# Power_Supply.net
KiCad netlist of a schematic drawn in Altium Designer
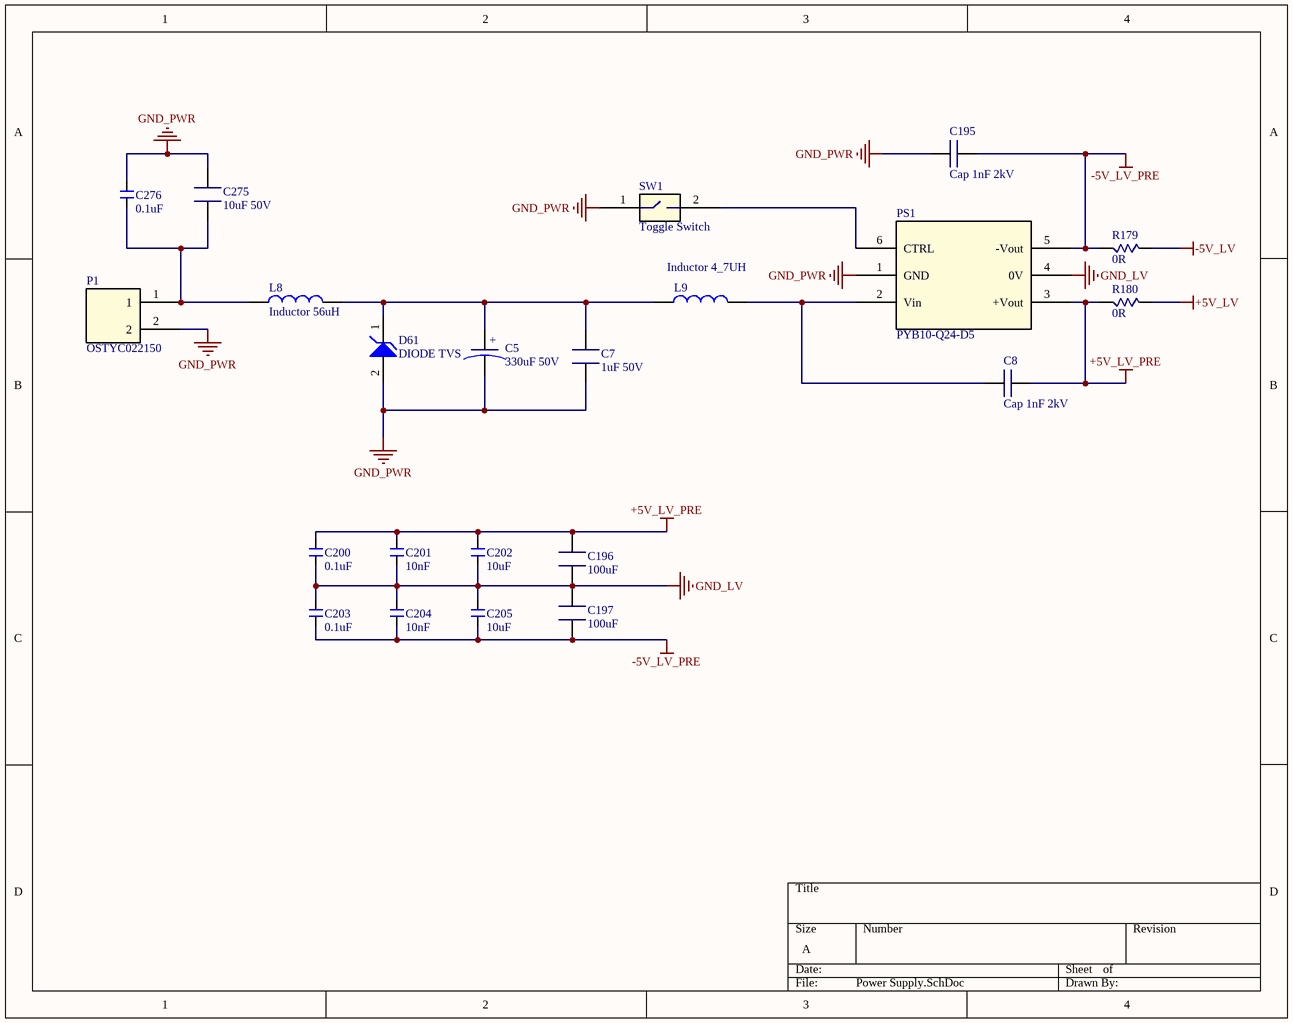
[diagram p0: Power Supply.SchDoc]

(export (version "E")
  (design (tool "Eeschema 10.0.6"))
  (components
    (comp (ref "C5")
      (value "330uF 50V")
      (footprint "Panasonic ECA-1HM331")
      (description "Capacitor Aluminum 330uF 50V")
      (fields (field (name "PART") "P5184-ND"))
      (libsource (lib "Library_Microgrid") (part "Cap Alum 330uF 50V"))
    )
    (comp (ref "C7")
      (value "1uF 50V")
      (footprint "1206")
      (description "CAP CER 1UF 50V X7R 1206")
      (fields (field (name "PART") "1276-1068-1-ND") (field (name "Comment") "Cap 1206"))
      (libsource (lib "Library_Microgrid") (part "Cap 1206"))
    )
    (comp (ref "C8")
      (value "Cap 1nF 2kV")
      (footprint "1812 (4532 Metric)")
      (description "CAP CER 1000PF 2KV X7R 1812")
      (fields (field (name "PART") "399-3447-1-ND"))
      (libsource (lib "Library_Microgrid") (part "Cap 3kV 220pF"))
    )
    (comp (ref "C195")
      (value "Cap 1nF 2kV")
      (footprint "1812 (4532 Metric)")
      (description "CAP CER 1000PF 2KV X7R 1812")
      (fields (field (name "PART") "399-3447-1-ND"))
      (libsource (lib "Library_Microgrid") (part "Cap 3kV 220pF"))
    )
    (comp (ref "C196")
      (value "100uF")
      (footprint "1206")
      (description "CAP CER 100UF 10V JB 1206")
      (fields (field (name "PART") "445-11682-1-ND") (field (name "Comment") "Cap 1206"))
      (libsource (lib "Library_Microgrid") (part "Cap 1206"))
    )
    (comp (ref "C197")
      (value "100uF")
      (footprint "1206")
      (description "CAP CER 100UF 10V JB 1206")
      (fields (field (name "PART") "445-11682-1-ND") (field (name "Comment") "Cap 1206"))
      (libsource (lib "Library_Microgrid") (part "Cap 1206"))
    )
    (comp (ref "C200")
      (value "0.1uF")
      (footprint "0603 (1608 Metric)")
      (description "CAP CER 0.1UF 50V Y5V 0603")
      (fields (field (name "PART") "311-1343-6-ND") (field (name "Comment") "Cap 0603_new"))
      (libsource (lib "Library_Microgrid") (part "Cap 0603_new"))
    )
    (comp (ref "C201")
      (value "10nF")
      (footprint "0603 (1608 Metric)")
      (description "CAP CER 0603 10NF 50V U2J 5%")
      (fields (field (name "PART") "399-13384-1-ND") (field (name "Comment") "Cap 0603_new"))
      (libsource (lib "Library_Microgrid") (part "Cap 0603_new"))
    )
    (comp (ref "C202")
      (value "10uF")
      (footprint "0603 (1608 Metric)")
      (description "CAP CER 10UF 35V X5R 0805")
      (fields (field (name "PART") "490-10515-1-ND") (field (name "Comment") "Cap 0603_new"))
      (libsource (lib "Library_Microgrid") (part "Cap 0603_new"))
    )
    (comp (ref "C203")
      (value "0.1uF")
      (footprint "0603 (1608 Metric)")
      (description "CAP CER 0.1UF 50V Y5V 0603")
      (fields (field (name "PART") "311-1343-6-ND") (field (name "Comment") "Cap 0603_new"))
      (libsource (lib "Library_Microgrid") (part "Cap 0603_new"))
    )
    (comp (ref "C204")
      (value "10nF")
      (footprint "0603 (1608 Metric)")
      (description "CAP CER 0603 10NF 50V U2J 5%")
      (fields (field (name "PART") "399-13384-1-ND") (field (name "Comment") "Cap 0603_new"))
      (libsource (lib "Library_Microgrid") (part "Cap 0603_new"))
    )
    (comp (ref "C205")
      (value "10uF")
      (footprint "0603 (1608 Metric)")
      (description "CAP CER 10UF 35V X5R 0805")
      (fields (field (name "PART") "490-10515-1-ND") (field (name "Comment") "Cap 0603_new"))
      (libsource (lib "Library_Microgrid") (part "Cap 0603_new"))
    )
    (comp (ref "C275")
      (value "10uF 50V")
      (footprint "1206")
      (description "CAP CER 10UF 50V X5R 1206")
      (fields (field (name "PART") "587-3248-1-ND") (field (name "Comment") "Cap 1206"))
      (libsource (lib "Library_Microgrid") (part "Cap 1206"))
    )
    (comp (ref "C276")
      (value "0.1uF")
      (footprint "0603 (1608 Metric)")
      (description "CAP CER 0.1UF 50V Y5V 0603")
      (fields (field (name "PART") "311-1343-6-ND") (field (name "Comment") "Cap 0603_new"))
      (libsource (lib "Library_Microgrid") (part "Cap 0603_new"))
    )
    (comp (ref "D61")
      (value "DIODE TVS")
      (footprint "SMCJ48A")
      (fields (field (name "PART") "495-2402-ND"))
      (libsource (lib "Library_Microgrid") (part "DIODE TVS"))
    )
    (comp (ref "L8")
      (value "Inductor 56uH")
      (footprint "Ind SM 56UH")
      (description "FIXED IND 56UH 700MA 481 MOHM")
      (fields (field (name "PART") "732-4102-1-ND"))
      (libsource (lib "Library_Microgrid") (part "Inductor 10uH"))
    )
    (comp (ref "L9")
      (value "Inductor 4_7UH")
      (footprint "Ind SM 4_7UH")
      (description "FIXED IND 4.7UH 1.2A 105 MOHM")
      (fields (field (name "PART") "732-1008-1-ND"))
      (libsource (lib "Library_Microgrid") (part "Inductor 10uH"))
    )
    (comp (ref "P1")
      (value "OSTYC022150")
      (footprint "2 pin Terminal")
      (description "2 pin Terminal")
      (fields (field (name "PART") "ED2902-ND"))
      (libsource (lib "Library_Microgrid") (part "2 pin Terminal"))
    )
    (comp (ref "PS1")
      (value "PYB10-Q24-D5")
      (footprint "6-DIP Module")
      (description "DC/DC CONVERTER +/-5V 10W")
      (fields (field (name "PART") "102-2849-ND"))
      (libsource (lib "Library_Microgrid") (part "PYB10-Q24-D5"))
    )
    (comp (ref "R179")
      (value "0R")
      (footprint "1206")
      (description "Resistor 1206")
      (libsource (lib "Library_Microgrid") (part "Resistor 1206"))
    )
    (comp (ref "R180")
      (value "0R")
      (footprint "1206")
      (description "Resistor 1206")
      (libsource (lib "Library_Microgrid") (part "Resistor 1206"))
    )
    (comp (ref "SW1")
      (value "Toggle Switch")
      (footprint "Toggle SW")
      (fields (field (name "PART") "360-3289-ND"))
      (libsource (lib "Library_Microgrid") (part "Toggle Switch"))
    )
  )
  (nets
    (net (code "1") (name "+5V_LV") (class "Default")
      (node (ref "R180") (pin "2") (pinfunction "A_2") (pintype "passive"))
    )
    (net (code "2") (name "+5V_LV_PRE") (class "Default")
      (node (ref "C196") (pin "2") (pinfunction "OUT_2") (pintype "passive"))
      (node (ref "C200") (pin "2") (pinfunction "OUT_2") (pintype "passive"))
      (node (ref "C201") (pin "2") (pinfunction "OUT_2") (pintype "passive"))
      (node (ref "C202") (pin "2") (pinfunction "OUT_2") (pintype "passive"))
      (node (ref "C8") (pin "2") (pinfunction "OUT_2") (pintype "passive"))
      (node (ref "PS1") (pin "3") (pinfunction "+Vout_3") (pintype "passive"))
      (node (ref "R180") (pin "1") (pinfunction "A_1") (pintype "passive"))
    )
    (net (code "3") (name "-5V_LV") (class "Default")
      (node (ref "R179") (pin "2") (pinfunction "A_2") (pintype "passive"))
    )
    (net (code "4") (name "-5V_LV_PRE") (class "Default")
      (node (ref "C195") (pin "2") (pinfunction "OUT_2") (pintype "passive"))
      (node (ref "C197") (pin "1") (pinfunction "OUT_1") (pintype "passive"))
      (node (ref "C203") (pin "1") (pinfunction "OUT_1") (pintype "passive"))
      (node (ref "C204") (pin "1") (pinfunction "OUT_1") (pintype "passive"))
      (node (ref "C205") (pin "1") (pinfunction "OUT_1") (pintype "passive"))
      (node (ref "PS1") (pin "5") (pinfunction "-Vout_5") (pintype "passive"))
      (node (ref "R179") (pin "1") (pinfunction "A_1") (pintype "passive"))
    )
    (net (code "5") (name "GND_LV") (class "Default")
      (node (ref "C196") (pin "1") (pinfunction "OUT_1") (pintype "passive"))
      (node (ref "C197") (pin "2") (pinfunction "OUT_2") (pintype "passive"))
      (node (ref "C200") (pin "1") (pinfunction "OUT_1") (pintype "passive"))
      (node (ref "C201") (pin "1") (pinfunction "OUT_1") (pintype "passive"))
      (node (ref "C202") (pin "1") (pinfunction "OUT_1") (pintype "passive"))
      (node (ref "C203") (pin "2") (pinfunction "OUT_2") (pintype "passive"))
      (node (ref "C204") (pin "2") (pinfunction "OUT_2") (pintype "passive"))
      (node (ref "C205") (pin "2") (pinfunction "OUT_2") (pintype "passive"))
      (node (ref "PS1") (pin "4") (pinfunction "0V_4") (pintype "passive"))
    )
    (net (code "6") (name "GND_PWR") (class "Default")
      (node (ref "C195") (pin "1") (pinfunction "OUT_1") (pintype "passive"))
      (node (ref "C275") (pin "2") (pinfunction "OUT_2") (pintype "passive"))
      (node (ref "C276") (pin "2") (pinfunction "OUT_2") (pintype "passive"))
      (node (ref "C5") (pin "2") (pinfunction "OUT_2") (pintype "passive"))
      (node (ref "C7") (pin "1") (pinfunction "OUT_1") (pintype "passive"))
      (node (ref "D61") (pin "2") (pinfunction "Anode_2") (pintype "passive"))
      (node (ref "P1") (pin "2") (pinfunction "2_2") (pintype "passive"))
      (node (ref "PS1") (pin "1") (pinfunction "GND_1") (pintype "passive"))
      (node (ref "SW1") (pin "1") (pinfunction "1_1") (pintype "passive"))
    )
    (net (code "7") (name "Net-(C5-OUT-Pad1)") (class "Default")
      (node (ref "C5") (pin "1") (pinfunction "OUT_1") (pintype "passive"))
      (node (ref "C7") (pin "2") (pinfunction "OUT_2") (pintype "passive"))
      (node (ref "D61") (pin "1") (pinfunction "Anode_1") (pintype "passive"))
      (node (ref "L8") (pin "2") (pinfunction "OUT_2") (pintype "passive"))
      (node (ref "L9") (pin "1") (pinfunction "OUT_1") (pintype "passive"))
    )
    (net (code "8") (name "Net-(C275-OUT-Pad1)") (class "Default")
      (node (ref "C275") (pin "1") (pinfunction "OUT_1") (pintype "passive"))
      (node (ref "C276") (pin "1") (pinfunction "OUT_1") (pintype "passive"))
      (node (ref "L8") (pin "1") (pinfunction "OUT_1") (pintype "passive"))
      (node (ref "P1") (pin "1") (pinfunction "1_1") (pintype "passive"))
    )
    (net (code "9") (name "Net-(PS1-CTRL)") (class "Default")
      (node (ref "PS1") (pin "6") (pinfunction "CTRL_6") (pintype "passive"))
      (node (ref "SW1") (pin "2") (pinfunction "2_2") (pintype "passive"))
    )
    (net (code "10") (name "Net-(PS1-Vin)") (class "Default")
      (node (ref "C8") (pin "1") (pinfunction "OUT_1") (pintype "passive"))
      (node (ref "L9") (pin "2") (pinfunction "OUT_2") (pintype "passive"))
      (node (ref "PS1") (pin "2") (pinfunction "Vin_2") (pintype "passive"))
    )
  )
)
